# 7_peripherals.net
KiCad netlist of a schematic drawn in Altium Designer
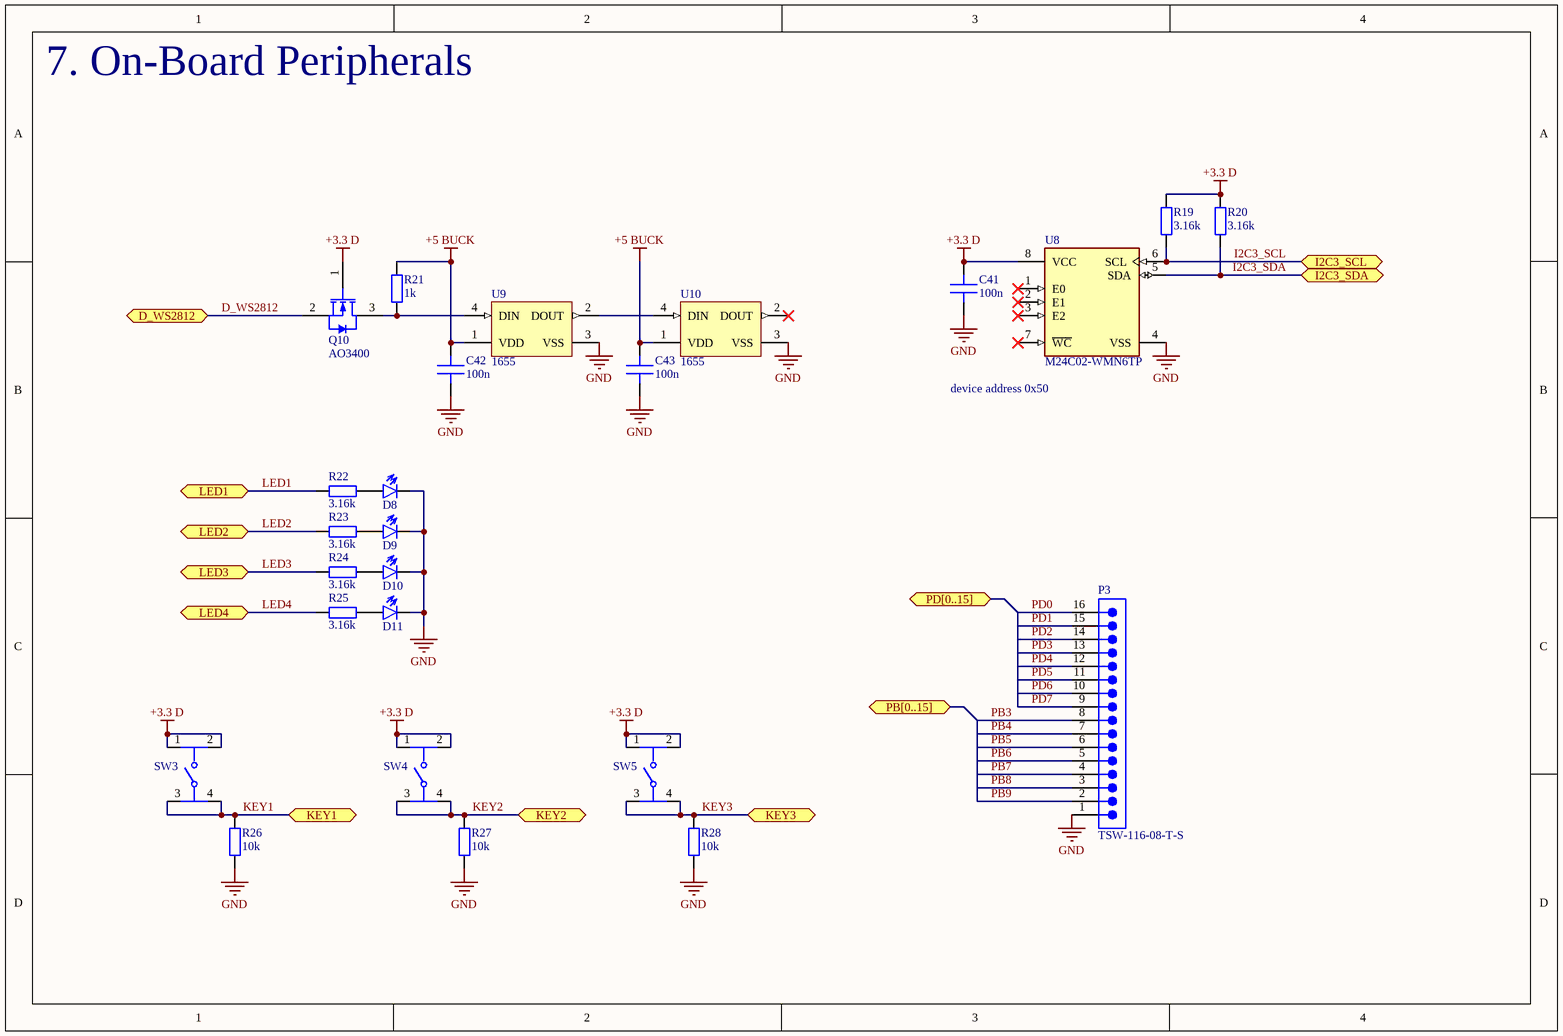
[diagram p0: 7_peripherals.SchDoc]

(export (version "E")
  (design (tool "Eeschema 10.0.6"))
  (components
    (comp (ref "C41")
      (value "100n")
      (footprint "IPC C C0402 NO SILK")
      (libsource (lib "JLCPCB Library") (part "Generic CAP 0402"))
    )
    (comp (ref "C42")
      (value "100n")
      (footprint "IPC C C0402 NO SILK")
      (libsource (lib "JLCPCB Library") (part "Generic CAP 0402"))
    )
    (comp (ref "C43")
      (value "100n")
      (footprint "IPC C C0402 NO SILK")
      (libsource (lib "JLCPCB Library") (part "Generic CAP 0402"))
    )
    (comp (ref "D8")
      (value "Yellow LED 0603")
      (footprint "IPC C D0603")
      (libsource (lib "JLCPCB Library") (part "Generic LED 0603"))
    )
    (comp (ref "D9")
      (value "Yellow LED 0603")
      (footprint "IPC C D0603")
      (libsource (lib "JLCPCB Library") (part "Generic LED 0603"))
    )
    (comp (ref "D10")
      (value "Yellow LED 0603")
      (footprint "IPC C D0603")
      (libsource (lib "JLCPCB Library") (part "Generic LED 0603"))
    )
    (comp (ref "D11")
      (value "Yellow LED 0603")
      (footprint "IPC C D0603")
      (libsource (lib "JLCPCB Library") (part "Generic LED 0603"))
    )
    (comp (ref "P3")
      (value "TSW-116-08-T-S")
      (footprint "SMTC-TSW-116-08-X-S")
      (description "0.025\" SQ Post Header, Through-hole, Vertical, -55 to 105 degC, 2.54 mm Pitch, 16-Pin, Male, RoHS")
      (fields (field (name "MANUFACTURER") "Samtec"))
      (libsource (lib "Altium Content Vault") (part "SMTC-TSW-116-08-X-S"))
    )
    (comp (ref "Q10")
      (value "AO3400")
      (footprint "AO-SOT23-3_V")
      (description "N-channel Enhancement Mode Field-Effect Transistor; 5.8A/30V")
      (fields (field (name "MANUFACTURER") "Alpha and Omega"))
      (libsource (lib "Altium Content Vault") (part "AO-NEMOS-G1S2D3-3"))
    )
    (comp (ref "R19")
      (value "3.16k")
      (footprint "IPC C R0402 NO SILK")
      (libsource (lib "JLCPCB Library") (part "Generic RES 0402"))
    )
    (comp (ref "R20")
      (value "3.16k")
      (footprint "IPC C R0402 NO SILK")
      (libsource (lib "JLCPCB Library") (part "Generic RES 0402"))
    )
    (comp (ref "R21")
      (value "1k")
      (footprint "IPC C R0402 NO SILK")
      (libsource (lib "JLCPCB Library") (part "Generic RES 0402"))
    )
    (comp (ref "R22")
      (value "3.16k")
      (footprint "IPC C R0402 NO SILK")
      (libsource (lib "JLCPCB Library") (part "Generic RES 0402"))
    )
    (comp (ref "R23")
      (value "3.16k")
      (footprint "IPC C R0402 NO SILK")
      (libsource (lib "JLCPCB Library") (part "Generic RES 0402"))
    )
    (comp (ref "R24")
      (value "3.16k")
      (footprint "IPC C R0402 NO SILK")
      (libsource (lib "JLCPCB Library") (part "Generic RES 0402"))
    )
    (comp (ref "R25")
      (value "3.16k")
      (footprint "IPC C R0402 NO SILK")
      (libsource (lib "JLCPCB Library") (part "Generic RES 0402"))
    )
    (comp (ref "R26")
      (value "10k")
      (footprint "IPC C R0402 NO SILK")
      (libsource (lib "JLCPCB Library") (part "Generic RES 0402"))
    )
    (comp (ref "R27")
      (value "10k")
      (footprint "IPC C R0402 NO SILK")
      (libsource (lib "JLCPCB Library") (part "Generic RES 0402"))
    )
    (comp (ref "R28")
      (value "10k")
      (footprint "IPC C R0402 NO SILK")
      (libsource (lib "JLCPCB Library") (part "Generic RES 0402"))
    )
    (comp (ref "SW3")
      (value "PTS810SJM250SMTRLFS")
      (footprint "FP-PTS810SJM250SMTRLFS-MFG")
      (description "SWITCH TACTILE SPST-NO 0.05A 16V")
      (libsource (lib "Altium Content Vault") (part "1adf0dd01260c80cf25a44bfd6b99ba"))
    )
    (comp (ref "SW4")
      (value "PTS810SJM250SMTRLFS")
      (footprint "FP-PTS810SJM250SMTRLFS-MFG")
      (description "SWITCH TACTILE SPST-NO 0.05A 16V")
      (libsource (lib "Altium Content Vault") (part "1adf0dd01260c80cf25a44bfd6b99ba"))
    )
    (comp (ref "SW5")
      (value "PTS810SJM250SMTRLFS")
      (footprint "FP-PTS810SJM250SMTRLFS-MFG")
      (description "SWITCH TACTILE SPST-NO 0.05A 16V")
      (libsource (lib "Altium Content Vault") (part "1adf0dd01260c80cf25a44bfd6b99ba"))
    )
    (comp (ref "U8")
      (value "M24C02-WMN6TP")
      (footprint "FP-SO8N-SO-A-MFG")
      (description "IC EEPROM 2K I2C 400KHZ 8SO")
      (fields
        (field (name "MANUFACTURER") "STMicroelectronics")
        (field (name "OCTOPART") "https://octopart.com/m24c02-wmn6tp-stmicroelectronics-55404516")
      )
      (libsource (lib "Altium Content Vault") (part "6c91e1c1613830ec3abd94c18390ae3"))
    )
    (comp (ref "U9")
      (value "1655")
      (footprint "ADA-RGB-1655_V")
      (fields (field (name "MANUFACTURER") "Adafruit-Industries-LLC"))
      (libsource (lib "Altium Content Vault") (part "ADA-RGB-1655-4"))
    )
    (comp (ref "U10")
      (value "1655")
      (footprint "ADA-RGB-1655_V")
      (fields (field (name "MANUFACTURER") "Adafruit-Industries-LLC"))
      (libsource (lib "Altium Content Vault") (part "ADA-RGB-1655-4"))
    )
  )
  (nets
    (net (code "18") (name "+3.3 D") (class "Default")
      (node (ref "C41") (pin "2") (pinfunction "2_2") (pintype "passive"))
      (node (ref "Q10") (pin "1") (pinfunction "G_1") (pintype "passive"))
      (node (ref "R19") (pin "2") (pinfunction "2_2") (pintype "passive"))
      (node (ref "R20") (pin "2") (pinfunction "2_2") (pintype "passive"))
      (node (ref "SW3") (pin "1") (pinfunction "1_1") (pintype "passive"))
      (node (ref "SW3") (pin "2") (pinfunction "2_2") (pintype "passive"))
      (node (ref "SW4") (pin "1") (pinfunction "1_1") (pintype "passive"))
      (node (ref "SW4") (pin "2") (pinfunction "2_2") (pintype "passive"))
      (node (ref "SW5") (pin "1") (pinfunction "1_1") (pintype "passive"))
      (node (ref "SW5") (pin "2") (pinfunction "2_2") (pintype "passive"))
      (node (ref "U8") (pin "8") (pinfunction "VCC_8") (pintype "power_in"))
    )
    (net (code "19") (name "+5 BUCK") (class "Default")
      (node (ref "C42") (pin "2") (pinfunction "2_2") (pintype "passive"))
      (node (ref "C43") (pin "2") (pinfunction "2_2") (pintype "passive"))
      (node (ref "R21") (pin "2") (pinfunction "2_2") (pintype "passive"))
      (node (ref "U10") (pin "1") (pinfunction "VDD_1") (pintype "power_in"))
      (node (ref "U9") (pin "1") (pinfunction "VDD_1") (pintype "power_in"))
    )
    (net (code "20") (name "/D_WS2812") (class "Default")
      (node (ref "Q10") (pin "2") (pinfunction "S_2") (pintype "passive"))
    )
    (net (code "21") (name "/I2C3_SCL") (class "Default")
      (node (ref "R19") (pin "1") (pinfunction "1_1") (pintype "passive"))
      (node (ref "U8") (pin "6") (pinfunction "SCL_6") (pintype "input"))
    )
    (net (code "22") (name "/I2C3_SDA") (class "Default")
      (node (ref "R20") (pin "1") (pinfunction "1_1") (pintype "passive"))
      (node (ref "U8") (pin "5") (pinfunction "SDA_5") (pintype "bidirectional"))
    )
    (net (code "23") (name "/KEY1") (class "Default")
      (node (ref "R26") (pin "1") (pinfunction "1_1") (pintype "passive"))
      (node (ref "SW3") (pin "3") (pinfunction "3_3") (pintype "passive"))
      (node (ref "SW3") (pin "4") (pinfunction "4_4") (pintype "passive"))
    )
    (net (code "24") (name "/KEY2") (class "Default")
      (node (ref "R27") (pin "1") (pinfunction "1_1") (pintype "passive"))
      (node (ref "SW4") (pin "3") (pinfunction "3_3") (pintype "passive"))
      (node (ref "SW4") (pin "4") (pinfunction "4_4") (pintype "passive"))
    )
    (net (code "25") (name "/KEY3") (class "Default")
      (node (ref "R28") (pin "1") (pinfunction "1_1") (pintype "passive"))
      (node (ref "SW5") (pin "3") (pinfunction "3_3") (pintype "passive"))
      (node (ref "SW5") (pin "4") (pinfunction "4_4") (pintype "passive"))
    )
    (net (code "26") (name "/LED1") (class "Default")
      (node (ref "R22") (pin "2") (pinfunction "2_2") (pintype "passive"))
    )
    (net (code "27") (name "/LED2") (class "Default")
      (node (ref "R23") (pin "2") (pinfunction "2_2") (pintype "passive"))
    )
    (net (code "28") (name "/LED3") (class "Default")
      (node (ref "R24") (pin "2") (pinfunction "2_2") (pintype "passive"))
    )
    (net (code "29") (name "/LED4") (class "Default")
      (node (ref "R25") (pin "2") (pinfunction "2_2") (pintype "passive"))
    )
    (net (code "30") (name "/PB3") (class "Default")
      (node (ref "P3") (pin "8") (pinfunction "8_8") (pintype "passive"))
    )
    (net (code "31") (name "/PB4") (class "Default")
      (node (ref "P3") (pin "7") (pinfunction "7_7") (pintype "passive"))
    )
    (net (code "32") (name "/PB5") (class "Default")
      (node (ref "P3") (pin "6") (pinfunction "6_6") (pintype "passive"))
    )
    (net (code "33") (name "/PB6") (class "Default")
      (node (ref "P3") (pin "5") (pinfunction "5_5") (pintype "passive"))
    )
    (net (code "34") (name "/PB7") (class "Default")
      (node (ref "P3") (pin "4") (pinfunction "4_4") (pintype "passive"))
    )
    (net (code "35") (name "/PB8") (class "Default")
      (node (ref "P3") (pin "3") (pinfunction "3_3") (pintype "passive"))
    )
    (net (code "36") (name "/PB9") (class "Default")
      (node (ref "P3") (pin "2") (pinfunction "2_2") (pintype "passive"))
    )
    (net (code "38") (name "/PD0") (class "Default")
      (node (ref "P3") (pin "16") (pinfunction "16_16") (pintype "passive"))
    )
    (net (code "39") (name "/PD1") (class "Default")
      (node (ref "P3") (pin "15") (pinfunction "15_15") (pintype "passive"))
    )
    (net (code "40") (name "/PD2") (class "Default")
      (node (ref "P3") (pin "14") (pinfunction "14_14") (pintype "passive"))
    )
    (net (code "41") (name "/PD3") (class "Default")
      (node (ref "P3") (pin "13") (pinfunction "13_13") (pintype "passive"))
    )
    (net (code "42") (name "/PD4") (class "Default")
      (node (ref "P3") (pin "12") (pinfunction "12_12") (pintype "passive"))
    )
    (net (code "43") (name "/PD5") (class "Default")
      (node (ref "P3") (pin "11") (pinfunction "11_11") (pintype "passive"))
    )
    (net (code "44") (name "/PD6") (class "Default")
      (node (ref "P3") (pin "10") (pinfunction "10_10") (pintype "passive"))
    )
    (net (code "45") (name "/PD7") (class "Default")
      (node (ref "P3") (pin "9") (pinfunction "9_9") (pintype "passive"))
    )
    (net (code "47") (name "GND") (class "Default")
      (node (ref "C41") (pin "1") (pinfunction "1_1") (pintype "passive"))
      (node (ref "C42") (pin "1") (pinfunction "1_1") (pintype "passive"))
      (node (ref "C43") (pin "1") (pinfunction "1_1") (pintype "passive"))
      (node (ref "D10") (pin "2") (pinfunction "C_2") (pintype "passive"))
      (node (ref "D11") (pin "2") (pinfunction "C_2") (pintype "passive"))
      (node (ref "D8") (pin "2") (pinfunction "C_2") (pintype "passive"))
      (node (ref "D9") (pin "2") (pinfunction "C_2") (pintype "passive"))
      (node (ref "P3") (pin "1") (pinfunction "1_1") (pintype "passive"))
      (node (ref "R26") (pin "2") (pinfunction "2_2") (pintype "passive"))
      (node (ref "R27") (pin "2") (pinfunction "2_2") (pintype "passive"))
      (node (ref "R28") (pin "2") (pinfunction "2_2") (pintype "passive"))
      (node (ref "U10") (pin "3") (pinfunction "VSS_3") (pintype "power_in"))
      (node (ref "U8") (pin "4") (pinfunction "VSS_4") (pintype "power_in"))
      (node (ref "U9") (pin "3") (pinfunction "VSS_3") (pintype "power_in"))
    )
    (net (code "48") (name "Net-(D8-A)") (class "Default")
      (node (ref "D8") (pin "1") (pinfunction "A_1") (pintype "passive"))
      (node (ref "R22") (pin "1") (pinfunction "1_1") (pintype "passive"))
    )
    (net (code "49") (name "Net-(D9-A)") (class "Default")
      (node (ref "D9") (pin "1") (pinfunction "A_1") (pintype "passive"))
      (node (ref "R23") (pin "1") (pinfunction "1_1") (pintype "passive"))
    )
    (net (code "50") (name "Net-(D10-A)") (class "Default")
      (node (ref "D10") (pin "1") (pinfunction "A_1") (pintype "passive"))
      (node (ref "R24") (pin "1") (pinfunction "1_1") (pintype "passive"))
    )
    (net (code "51") (name "Net-(D11-A)") (class "Default")
      (node (ref "D11") (pin "1") (pinfunction "A_1") (pintype "passive"))
      (node (ref "R25") (pin "1") (pinfunction "1_1") (pintype "passive"))
    )
    (net (code "52") (name "Net-(Q10-D)") (class "Default")
      (node (ref "Q10") (pin "3") (pinfunction "D_3") (pintype "passive"))
      (node (ref "R21") (pin "1") (pinfunction "1_1") (pintype "passive"))
      (node (ref "U9") (pin "4") (pinfunction "DIN_4") (pintype "input"))
    )
    (net (code "53") (name "Net-(U10-DIN)") (class "Default")
      (node (ref "U10") (pin "4") (pinfunction "DIN_4") (pintype "input"))
      (node (ref "U9") (pin "2") (pinfunction "DOUT_2") (pintype "output"))
    )
    (net (code "54") (name "unconnected-(U8-E0-Pad1)") (class "Default")
      (node (ref "U8") (pin "1") (pinfunction "E0_1") (pintype "input+no_connect"))
    )
    (net (code "55") (name "unconnected-(U8-E1-Pad2)") (class "Default")
      (node (ref "U8") (pin "2") (pinfunction "E1_2") (pintype "input+no_connect"))
    )
    (net (code "56") (name "unconnected-(U8-E2-Pad3)") (class "Default")
      (node (ref "U8") (pin "3") (pinfunction "E2_3") (pintype "input+no_connect"))
    )
    (net (code "57") (name "unconnected-(U8-~{WC}-Pad7)") (class "Default")
      (node (ref "U8") (pin "7") (pinfunction "~{WC}_7") (pintype "input+no_connect"))
    )
    (net (code "58") (name "unconnected-(U10-DOUT-Pad2)") (class "Default")
      (node (ref "U10") (pin "2") (pinfunction "DOUT_2") (pintype "output+no_connect"))
    )
  )
)
